# sensors.net
KiCad netlist of a schematic drawn in EAGLE
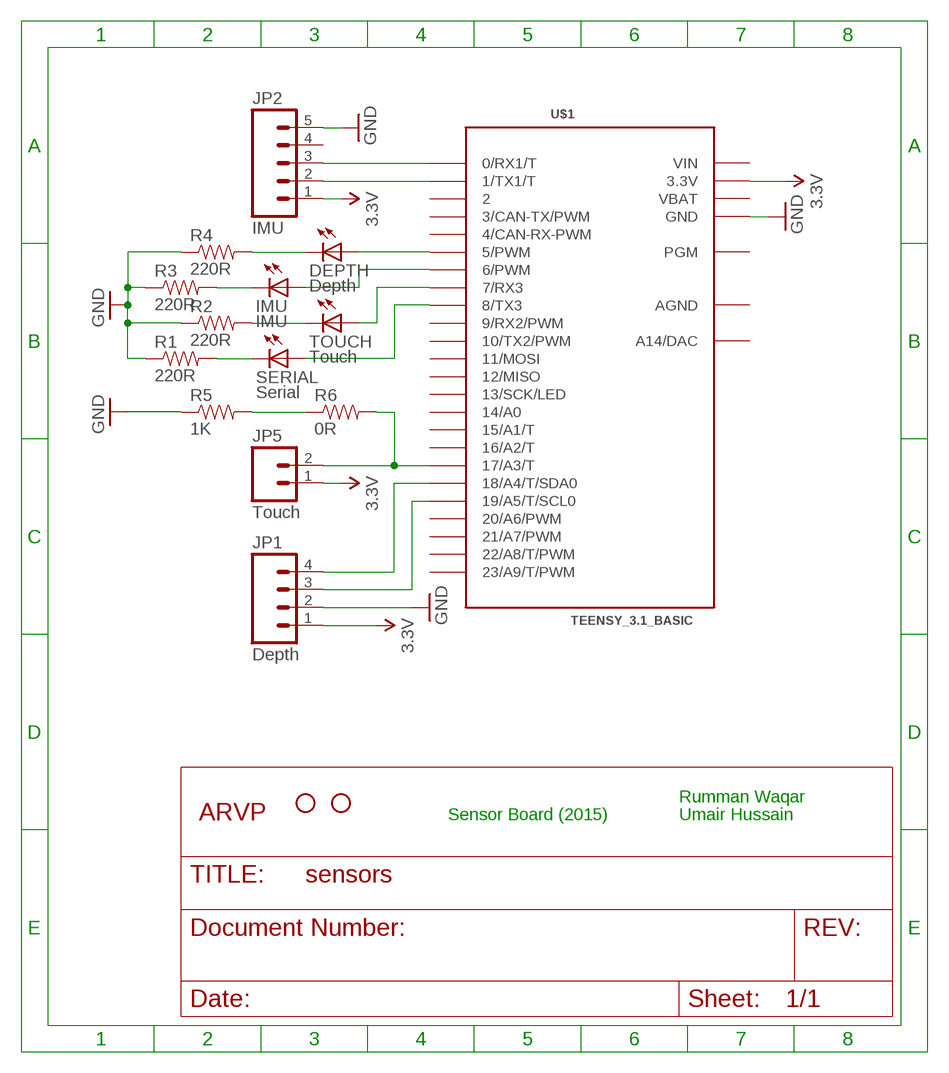
[diagram p0: schematic, sheet 1]

(export (version "E")
  (design (tool "Eeschema 10.0.6"))
  (components
    (comp (ref "DEPTH")
      (value "Depth")
      (footprint "eagle-import:LED-1206")
      (libsource (lib "eagle-import") (part "LED1206"))
    )
    (comp (ref "IMU")
      (value "IMU")
      (footprint "eagle-import:LED-1206")
      (libsource (lib "eagle-import") (part "LED1206"))
    )
    (comp (ref "JP1")
      (value "Depth")
      (footprint "eagle-import:1X04_LONGPADS")
      (libsource (lib "eagle-import") (part "M04LONGPADS"))
    )
    (comp (ref "JP2")
      (value "IMU")
      (footprint "eagle-import:1X05_LONGPADS")
      (libsource (lib "eagle-import") (part "M05PTH_LONGPADS"))
    )
    (comp (ref "JP3")
      (value "STAND-OFF")
      (footprint "eagle-import:STAND-OFF")
      (libsource (lib "eagle-import") (part "STAND-OFF"))
    )
    (comp (ref "JP4")
      (value "STAND-OFF")
      (footprint "eagle-import:STAND-OFF")
      (libsource (lib "eagle-import") (part "STAND-OFF"))
    )
    (comp (ref "JP5")
      (value "Touch")
      (footprint "eagle-import:MOLEX-1X2")
      (libsource (lib "eagle-import") (part "M02POLAR"))
    )
    (comp (ref "R1")
      (value "220R")
      (footprint "eagle-import:1206")
      (libsource (lib "eagle-import") (part "RESISTOR1206"))
    )
    (comp (ref "R2")
      (value "220R")
      (footprint "eagle-import:1206")
      (libsource (lib "eagle-import") (part "RESISTOR1206"))
    )
    (comp (ref "R3")
      (value "220R")
      (footprint "eagle-import:1206")
      (libsource (lib "eagle-import") (part "RESISTOR1206"))
    )
    (comp (ref "R4")
      (value "220R")
      (footprint "eagle-import:1206")
      (libsource (lib "eagle-import") (part "RESISTOR1206"))
    )
    (comp (ref "R5")
      (value "1K")
      (footprint "eagle-import:1206")
      (libsource (lib "eagle-import") (part "RESISTOR1206"))
    )
    (comp (ref "R6")
      (value "0R")
      (footprint "eagle-import:1206")
      (libsource (lib "eagle-import") (part "RESISTOR1206"))
    )
    (comp (ref "SERIAL")
      (value "Serial")
      (footprint "eagle-import:LED-1206")
      (libsource (lib "eagle-import") (part "LED1206"))
    )
    (comp (ref "TOUCH")
      (value "Touch")
      (footprint "eagle-import:LED-1206")
      (libsource (lib "eagle-import") (part "LED1206"))
    )
    (comp (ref "U$1")
      (value "TEENSY_3.1_BASIC")
      (footprint "eagle-import:TEENSY_3.1_BASIC")
      (libsource (lib "eagle-import") (part "TEENSY_3.1_BASIC"))
    )
    (comp (ref "U$2")
      (value "ARVP_LOGO")
      (footprint "eagle-import:ARVP")
      (libsource (lib "eagle-import") (part "ARVP_LOGO"))
    )
  )
  (nets
    (net (code "1") (name "/AGND") (class "Default")
      (node (ref "U$1") (pin "AGND") (pinfunction "AGND_AGND") (pintype "power_in"))
    )
    (net (code "2") (name "/VBAT") (class "Default")
      (node (ref "U$1") (pin "VBAT") (pinfunction "VBAT_VBAT") (pintype "power_in"))
    )
    (net (code "3") (name "/VIN") (class "Default")
      (node (ref "U$1") (pin "VIN") (pinfunction "VIN_VIN") (pintype "power_in"))
    )
    (net (code "4") (name "3.3V") (class "Default")
      (node (ref "JP1") (pin "1") (pinfunction "1_1") (pintype "passive"))
      (node (ref "JP2") (pin "1") (pinfunction "1_1") (pintype "passive"))
      (node (ref "JP5") (pin "1") (pinfunction "1_1") (pintype "passive"))
      (node (ref "U$1") (pin "3.3V") (pinfunction "3.3V_3.3V") (pintype "power_in"))
      (node (ref "U$1") (pin "3.3V1") (pinfunction "3.3V_3.3V1") (pintype "power_in"))
    )
    (net (code "5") (name "GND") (class "Default")
      (node (ref "JP1") (pin "2") (pinfunction "2_2") (pintype "passive"))
      (node (ref "JP2") (pin "5") (pinfunction "5_5") (pintype "passive"))
      (node (ref "R1") (pin "1") (pinfunction "1_1") (pintype "passive"))
      (node (ref "R2") (pin "1") (pinfunction "1_1") (pintype "passive"))
      (node (ref "R3") (pin "1") (pinfunction "1_1") (pintype "passive"))
      (node (ref "R4") (pin "1") (pinfunction "1_1") (pintype "passive"))
      (node (ref "R5") (pin "1") (pinfunction "1_1") (pintype "passive"))
      (node (ref "U$1") (pin "GND") (pinfunction "GND_GND") (pintype "power_in"))
      (node (ref "U$1") (pin "GND1") (pinfunction "GND_GND1") (pintype "power_in"))
    )
    (net (code "6") (name "Net-(DEPTH-PadC)") (class "Default")
      (node (ref "DEPTH") (pin "C") (pinfunction "C_C") (pintype "passive"))
      (node (ref "R4") (pin "2") (pinfunction "2_2") (pintype "passive"))
    )
    (net (code "7") (name "Net-(IMU-PadC)") (class "Default")
      (node (ref "IMU") (pin "C") (pinfunction "C_C") (pintype "passive"))
      (node (ref "R3") (pin "2") (pinfunction "2_2") (pintype "passive"))
    )
    (net (code "8") (name "Net-(R1-Pad2)") (class "Default")
      (node (ref "R1") (pin "2") (pinfunction "2_2") (pintype "passive"))
      (node (ref "SERIAL") (pin "C") (pinfunction "C_C") (pintype "passive"))
    )
    (net (code "9") (name "Net-(R2-Pad2)") (class "Default")
      (node (ref "R2") (pin "2") (pinfunction "2_2") (pintype "passive"))
      (node (ref "TOUCH") (pin "C") (pinfunction "C_C") (pintype "passive"))
    )
    (net (code "10") (name "Net-(R5-Pad2)") (class "Default")
      (node (ref "R5") (pin "2") (pinfunction "2_2") (pintype "passive"))
      (node (ref "R6") (pin "1") (pinfunction "1_1") (pintype "passive"))
    )
    (net (code "11") (name "Net-(U$1-0{slash}RX1{slash}T)") (class "Default")
      (node (ref "JP2") (pin "3") (pinfunction "3_3") (pintype "passive"))
      (node (ref "U$1") (pin "0") (pinfunction "0/RX1/T_0") (pintype "bidirectional"))
    )
    (net (code "12") (name "Net-(U$1-1{slash}TX1{slash}T)") (class "Default")
      (node (ref "JP2") (pin "2") (pinfunction "2_2") (pintype "passive"))
      (node (ref "U$1") (pin "1") (pinfunction "1/TX1/T_1") (pintype "bidirectional"))
    )
    (net (code "13") (name "Net-(U$1-5{slash}PWM)") (class "Default")
      (node (ref "DEPTH") (pin "A") (pinfunction "A_A") (pintype "passive"))
      (node (ref "U$1") (pin "5") (pinfunction "5/PWM_5") (pintype "bidirectional"))
    )
    (net (code "14") (name "Net-(U$1-6{slash}PWM)") (class "Default")
      (node (ref "IMU") (pin "A") (pinfunction "A_A") (pintype "passive"))
      (node (ref "U$1") (pin "6") (pinfunction "6/PWM_6") (pintype "bidirectional"))
    )
    (net (code "15") (name "Net-(U$1-7{slash}RX3)") (class "Default")
      (node (ref "TOUCH") (pin "A") (pinfunction "A_A") (pintype "passive"))
      (node (ref "U$1") (pin "7") (pinfunction "7/RX3_7") (pintype "bidirectional"))
    )
    (net (code "16") (name "Net-(U$1-8{slash}TX3)") (class "Default")
      (node (ref "SERIAL") (pin "A") (pinfunction "A_A") (pintype "passive"))
      (node (ref "U$1") (pin "8") (pinfunction "8/TX3_8") (pintype "bidirectional"))
    )
    (net (code "17") (name "Net-(U$1-17{slash}A3{slash}T)") (class "Default")
      (node (ref "JP5") (pin "2") (pinfunction "2_2") (pintype "passive"))
      (node (ref "R6") (pin "2") (pinfunction "2_2") (pintype "passive"))
      (node (ref "U$1") (pin "17/A3") (pinfunction "17/A3/T_17/A3") (pintype "bidirectional"))
    )
    (net (code "18") (name "Net-(U$1-18{slash}A4{slash}T{slash}SDA0)") (class "Default")
      (node (ref "JP1") (pin "4") (pinfunction "4_4") (pintype "passive"))
      (node (ref "U$1") (pin "18/A4") (pinfunction "18/A4/T/SDA0_18/A4") (pintype "bidirectional"))
    )
    (net (code "19") (name "Net-(U$1-19{slash}A5{slash}T{slash}SCL0)") (class "Default")
      (node (ref "JP1") (pin "3") (pinfunction "3_3") (pintype "passive"))
      (node (ref "U$1") (pin "19/A5") (pinfunction "19/A5/T/SCL0_19/A5") (pintype "bidirectional"))
    )
    (net (code "20") (name "unconnected-(JP2-Pad4)") (class "Default")
      (node (ref "JP2") (pin "4") (pinfunction "4_4") (pintype "passive"))
    )
    (net (code "21") (name "unconnected-(U$1-3{slash}CAN-TX{slash}PWM-Pad3)") (class "Default")
      (node (ref "U$1") (pin "3") (pinfunction "3/CAN-TX/PWM_3") (pintype "bidirectional"))
    )
    (net (code "22") (name "unconnected-(U$1-4{slash}CAN-RX-PWM-Pad4)") (class "Default")
      (node (ref "U$1") (pin "4") (pinfunction "4/CAN-RX-PWM_4") (pintype "bidirectional"))
    )
    (net (code "23") (name "unconnected-(U$1-9{slash}RX2{slash}PWM-Pad9)") (class "Default")
      (node (ref "U$1") (pin "9") (pinfunction "9/RX2/PWM_9") (pintype "bidirectional"))
    )
    (net (code "24") (name "unconnected-(U$1-10{slash}TX2{slash}PWM-Pad10)") (class "Default")
      (node (ref "U$1") (pin "10") (pinfunction "10/TX2/PWM_10") (pintype "bidirectional"))
    )
    (net (code "25") (name "unconnected-(U$1-11{slash}MOSI-Pad11)") (class "Default")
      (node (ref "U$1") (pin "11") (pinfunction "11/MOSI_11") (pintype "bidirectional"))
    )
    (net (code "26") (name "unconnected-(U$1-12{slash}MISO-Pad12)") (class "Default")
      (node (ref "U$1") (pin "12") (pinfunction "12/MISO_12") (pintype "bidirectional"))
    )
    (net (code "27") (name "unconnected-(U$1-13{slash}SCK{slash}LED-Pad13)") (class "Default")
      (node (ref "U$1") (pin "13") (pinfunction "13/SCK/LED_13") (pintype "bidirectional"))
    )
    (net (code "28") (name "unconnected-(U$1-15{slash}A1{slash}T-Pad15{slash}A1)") (class "Default")
      (node (ref "U$1") (pin "15/A1") (pinfunction "15/A1/T_15/A1") (pintype "bidirectional"))
    )
    (net (code "29") (name "unconnected-(U$1-16{slash}A2{slash}T-Pad16{slash}A2)") (class "Default")
      (node (ref "U$1") (pin "16/A2") (pinfunction "16/A2/T_16/A2") (pintype "bidirectional"))
    )
    (net (code "30") (name "unconnected-(U$1-20{slash}A6{slash}PWM-Pad20{slash}A6)") (class "Default")
      (node (ref "U$1") (pin "20/A6") (pinfunction "20/A6/PWM_20/A6") (pintype "bidirectional"))
    )
    (net (code "31") (name "unconnected-(U$1-21{slash}A7{slash}PWM-Pad21{slash}A7)") (class "Default")
      (node (ref "U$1") (pin "21/A7") (pinfunction "21/A7/PWM_21/A7") (pintype "bidirectional"))
    )
    (net (code "32") (name "unconnected-(U$1-22{slash}A8{slash}T{slash}PWM-Pad22{slash}A8)") (class "Default")
      (node (ref "U$1") (pin "22/A8") (pinfunction "22/A8/T/PWM_22/A8") (pintype "bidirectional"))
    )
    (net (code "33") (name "unconnected-(U$1-23{slash}A9{slash}T{slash}PWM-Pad23{slash}A9)") (class "Default")
      (node (ref "U$1") (pin "23/A9") (pinfunction "23/A9/T/PWM_23/A9") (pintype "bidirectional"))
    )
    (net (code "34") (name "unconnected-(U$1-A14{slash}DAC-PadA14)") (class "Default")
      (node (ref "U$1") (pin "A14") (pinfunction "A14/DAC_A14") (pintype "bidirectional"))
    )
    (net (code "35") (name "unconnected-(U$1-Pad2)") (class "Default")
      (node (ref "U$1") (pin "2") (pinfunction "2_2") (pintype "bidirectional"))
    )
    (net (code "36") (name "unconnected-(U$1-Pad14{slash}A0)") (class "Default")
      (node (ref "U$1") (pin "14/A0") (pinfunction "14/A0_14/A0") (pintype "bidirectional"))
    )
    (net (code "37") (name "unconnected-(U$1-PadPGM)") (class "Default")
      (node (ref "U$1") (pin "PGM") (pinfunction "PGM_PGM") (pintype "bidirectional"))
    )
  )
)
